# CLK_GEN.net
KiCad netlist of a schematic drawn in Altium Designer
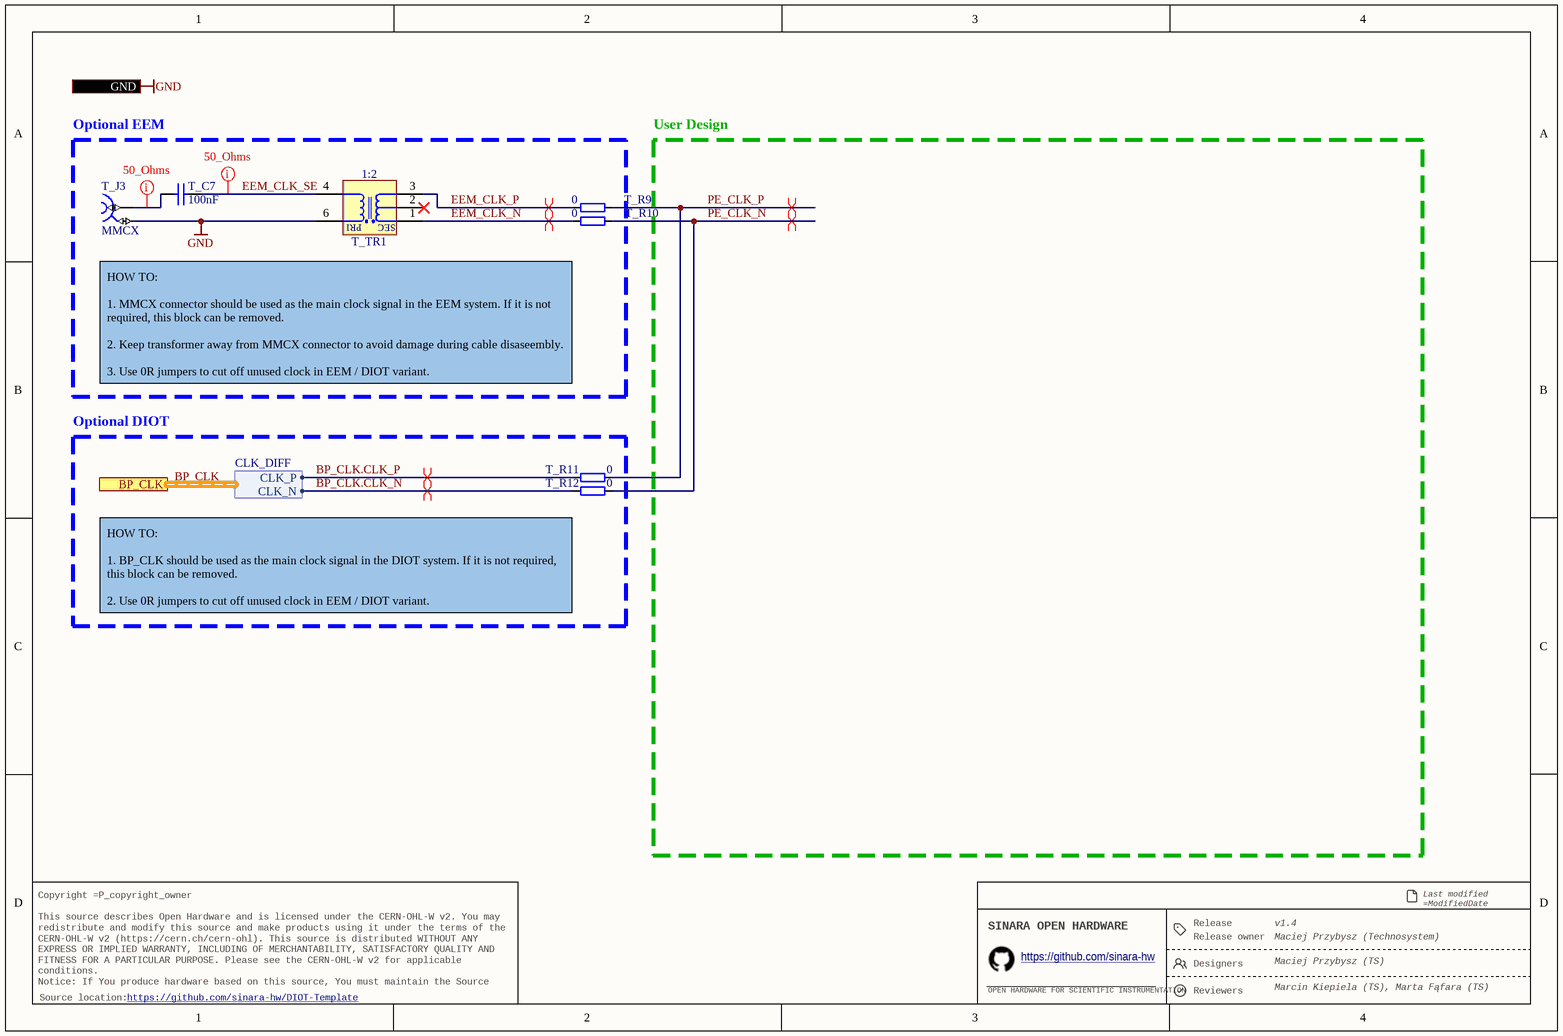
[diagram p0: CLK_GEN.SchDoc]

(export (version "E")
  (design (tool "Eeschema 10.0.6"))
  (components
    (comp (ref "T_C7")
      (value "100nF")
      (footprint "CAPC1005X55N")
      (description "Non-polarised capacitor")
      (fields
        (field (name "PART NUMBER") "CC0402_100NF_50V_10%_X7R")
        (field (name "VOLTAGE") "50V")
        (field (name "AUTHOR") "CERN DEM MR")
      )
      (libsource (lib "Capacitors") (part "Capacitor - non polarized"))
    )
    (comp (ref "T_J3")
      (value "MMCX")
      (footprint "SAMTEC_MMCX-J-P-H-ST-TH1")
      (fields
        (field (name "PART NUMBER") "SAMTEC_MMCX-J-P-H-ST-TH1")
        (field (name "MANUFACTURER") "SAMTEC")
        (field (name "MANUFACTURER PART NUMBER") "MMCX-J-P-H-ST-TH1")
        (field (name "AUTHOR") "CERN DEM JLC")
      )
      (libsource (lib "Connectors") (part "Coax_1Female_1Shield"))
    )
    (comp (ref "T_R9")
      (value "0")
      (footprint "RESC1005X40N")
      (description "Resistor")
      (fields
        (field (name "PART NUMBER") "R0402_0R_JUMPER")
        (field (name "MANUFACTURER") "GENERIC")
        (field (name "AUTHOR") "CERN DEM JLC")
      )
      (libsource (lib "Resistors") (part "Resistor"))
    )
    (comp (ref "T_R10")
      (value "0")
      (footprint "RESC1005X40N")
      (description "Resistor")
      (fields
        (field (name "PART NUMBER") "R0402_0R_JUMPER")
        (field (name "MANUFACTURER") "GENERIC")
        (field (name "AUTHOR") "CERN DEM JLC")
      )
      (libsource (lib "Resistors") (part "Resistor"))
    )
    (comp (ref "T_R11")
      (value "0")
      (footprint "RESC1005X40N")
      (description "Resistor")
      (fields
        (field (name "PART NUMBER") "R0402_0R_JUMPER")
        (field (name "MANUFACTURER") "GENERIC")
        (field (name "AUTHOR") "CERN DEM JLC")
      )
      (libsource (lib "Resistors") (part "Resistor"))
    )
    (comp (ref "T_R12")
      (value "0")
      (footprint "RESC1005X40N")
      (description "Resistor")
      (fields
        (field (name "PART NUMBER") "R0402_0R_JUMPER")
        (field (name "MANUFACTURER") "GENERIC")
        (field (name "AUTHOR") "CERN DEM JLC")
      )
      (libsource (lib "Resistors") (part "Resistor"))
    )
    (comp (ref "T_TR1")
      (value "1:2")
      (footprint "XFMR_MINI-CIRCUITS_DB714")
      (description "50 Ohms 3 to 300MHz RF Transformer")
      (fields
        (field (name "PART NUMBER") "XFMR_MINI-CIRCUITS_TCM2-1T")
        (field (name "POWER") "0.25W")
        (field (name "AUTHOR") "CERN DEM HF")
      )
      (libsource (lib "Inductors & Transformers") (part "XFMR_MINI-CIRCUITS_TCM2-1T"))
    )
  )
  (nets
    (net (code "2") (name "/BP_CLK.CLK_N") (class "Default")
      (node (ref "T_R12") (pin "1") (pinfunction "1_1") (pintype "passive"))
    )
    (net (code "3") (name "/BP_CLK.CLK_P") (class "Default")
      (node (ref "T_R11") (pin "1") (pinfunction "1_1") (pintype "passive"))
    )
    (net (code "5") (name "/EEM_CLK_N") (class "Default")
      (node (ref "T_R10") (pin "2") (pinfunction "2_2") (pintype "passive"))
      (node (ref "T_TR1") (pin "1") (pinfunction "SDOT_1") (pintype "passive"))
    )
    (net (code "6") (name "/EEM_CLK_P") (class "Default")
      (node (ref "T_R9") (pin "2") (pinfunction "2_2") (pintype "passive"))
      (node (ref "T_TR1") (pin "3") (pinfunction "S_3") (pintype "passive"))
    )
    (net (code "7") (name "/EEM_CLK_SE") (class "Default")
      (node (ref "T_C7") (pin "1") (pinfunction "1_1") (pintype "passive"))
      (node (ref "T_TR1") (pin "4") (pinfunction "P_4") (pintype "passive"))
    )
    (net (code "8") (name "/PE_CLK_N") (class "Default")
      (node (ref "T_R10") (pin "1") (pinfunction "1_1") (pintype "passive"))
      (node (ref "T_R12") (pin "2") (pinfunction "2_2") (pintype "passive"))
    )
    (net (code "9") (name "/PE_CLK_P") (class "Default")
      (node (ref "T_R11") (pin "2") (pinfunction "2_2") (pintype "passive"))
      (node (ref "T_R9") (pin "1") (pinfunction "1_1") (pintype "passive"))
    )
    (net (code "10") (name "GND") (class "Default")
      (node (ref "T_J3") (pin "2") (pinfunction "2_2") (pintype "bidirectional"))
      (node (ref "T_TR1") (pin "6") (pinfunction "PDOT_6") (pintype "passive"))
    )
    (net (code "11") (name "Net-(T_C7-Pad2)") (class "Default")
      (node (ref "T_C7") (pin "2") (pinfunction "2_2") (pintype "passive"))
      (node (ref "T_J3") (pin "1") (pinfunction "1_1") (pintype "bidirectional"))
    )
    (net (code "12") (name "unconnected-(T_TR1-NU-Pad2)") (class "Default")
      (node (ref "T_TR1") (pin "2") (pinfunction "NU_2") (pintype "passive+no_connect"))
    )
  )
)
